# OLM-base_v_REVG.net
KiCad netlist of a schematic drawn in EAGLE
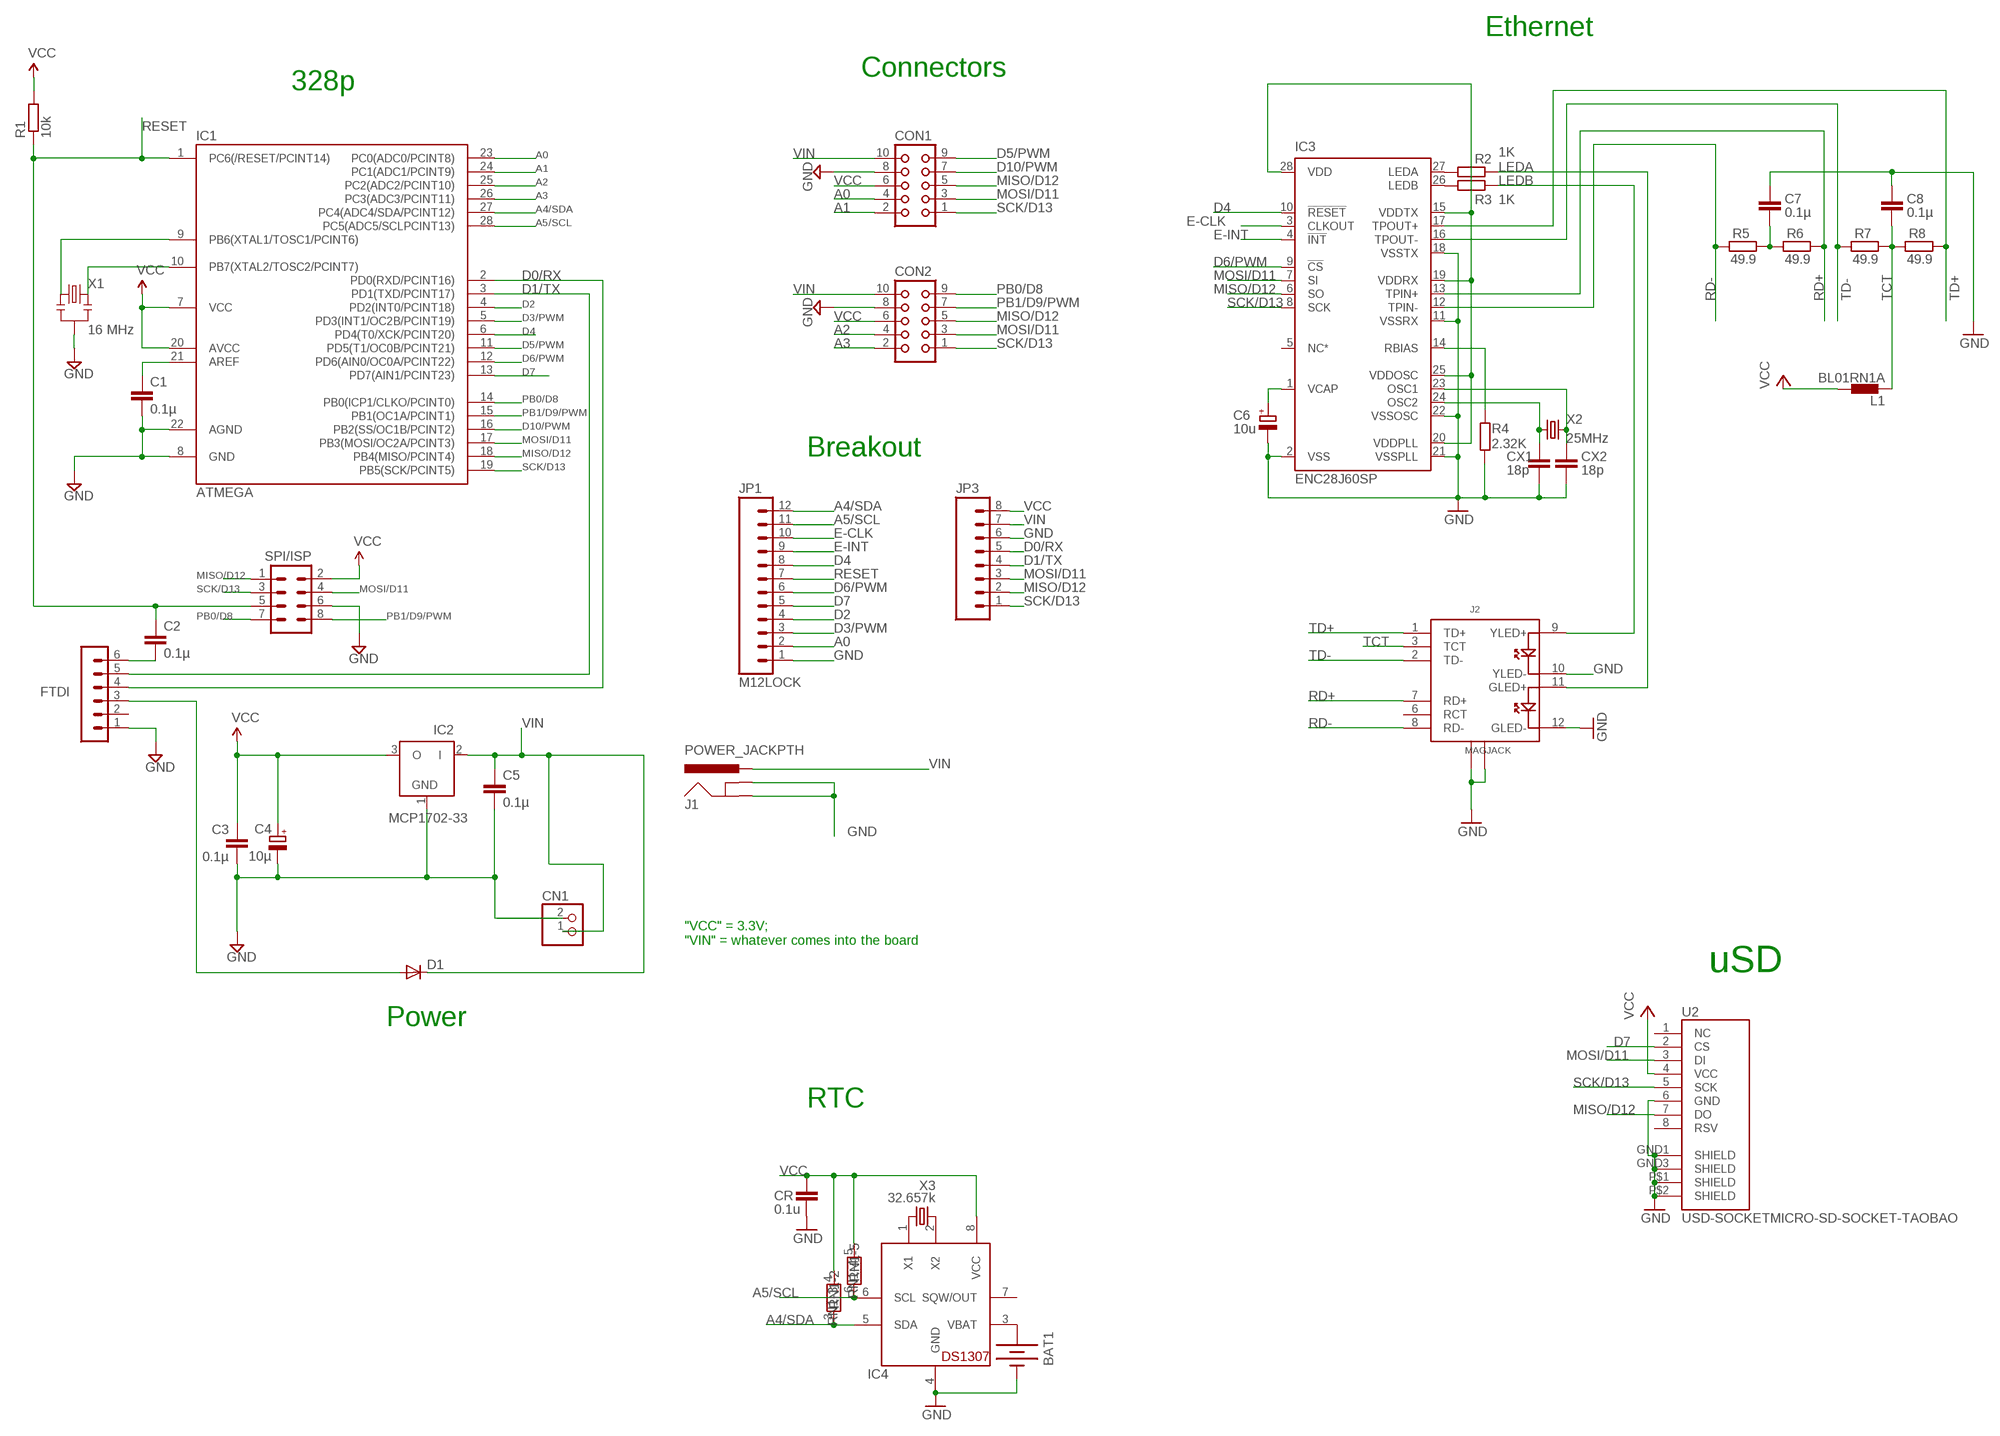
[diagram p0: schematic, sheet 1]

(export (version "E")
  (design (tool "Eeschema 10.0.6"))
  (components
    (comp (ref "BAT1")
      (value "BATTERY12PTH")
      (footprint "eagle-import:BATTCON_12MM_PTH")
      (libsource (lib "eagle-import") (part "BATTERY12PTH"))
    )
    (comp (ref "C1")
      (value "0.1µ")
      (footprint "eagle-import:C025-024X044")
      (libsource (lib "eagle-import") (part "resistor_C-EU025-024X044"))
    )
    (comp (ref "C2")
      (value "0.1µ")
      (footprint "eagle-import:C025-024X044")
      (libsource (lib "eagle-import") (part "resistor_C-EU025-024X044"))
    )
    (comp (ref "C3")
      (value "0.1µ")
      (footprint "eagle-import:C025-024X044")
      (libsource (lib "eagle-import") (part "resistor_C-EU025-024X044"))
    )
    (comp (ref "C4")
      (value "10µ")
      (footprint "eagle-import:E1,8-4")
      (libsource (lib "eagle-import") (part "CPOL-EUE1.8-4"))
    )
    (comp (ref "C5")
      (value "0.1µ")
      (footprint "eagle-import:C025-024X044")
      (libsource (lib "eagle-import") (part "resistor_C-EU025-024X044"))
    )
    (comp (ref "C6")
      (value "10u")
      (footprint "eagle-import:E1,8-4")
      (libsource (lib "eagle-import") (part "CPOL-EUE1.8-4"))
    )
    (comp (ref "C7")
      (value "0.1µ")
      (footprint "eagle-import:C025-024X044")
      (libsource (lib "eagle-import") (part "resistor_C-EU025-024X044"))
    )
    (comp (ref "C8")
      (value "0.1µ")
      (footprint "eagle-import:C025-024X044")
      (libsource (lib "eagle-import") (part "resistor_C-EU025-024X044"))
    )
    (comp (ref "CN1")
      (value "JST_2PIN-THM-RA")
      (footprint "eagle-import:JST-PH-2-THM-RA")
      (libsource (lib "eagle-import") (part "JST_2PIN-THM-RA"))
    )
    (comp (ref "CON1")
      (value "CON10L")
      (footprint "eagle-import:CON10L")
      (libsource (lib "eagle-import") (part "CON10L"))
    )
    (comp (ref "CON2")
      (value "CON10L")
      (footprint "eagle-import:CON10L")
      (libsource (lib "eagle-import") (part "CON10L"))
    )
    (comp (ref "CR")
      (value "0.1u")
      (footprint "eagle-import:C025-024X044")
      (libsource (lib "eagle-import") (part "C-EU025-024X044"))
    )
    (comp (ref "CX1")
      (value "18p")
      (footprint "eagle-import:C025-024X044")
      (libsource (lib "eagle-import") (part "resistor_C-EU025-024X044"))
    )
    (comp (ref "CX2")
      (value "18p")
      (footprint "eagle-import:C025-024X044")
      (libsource (lib "eagle-import") (part "resistor_C-EU025-024X044"))
    )
    (comp (ref "D1")
      (value "DIODE-D-5")
      (footprint "eagle-import:D-5")
      (libsource (lib "eagle-import") (part "DIODE-D-5"))
    )
    (comp (ref "FTDI")
      (value "FTDI")
      (footprint "eagle-import:MA06-1")
      (libsource (lib "eagle-import") (part "MA06-1"))
    )
    (comp (ref "IC1")
      (value "ATMEGA")
      (footprint "eagle-import:DIL28-3")
      (libsource (lib "eagle-import") (part "ATMEGA48/88/168-PU"))
    )
    (comp (ref "IC2")
      (value "MCP1702-33")
      (footprint "eagle-import:TO92")
      (libsource (lib "eagle-import") (part "MCP1702Z"))
    )
    (comp (ref "IC3")
      (value "ENC28J60SP")
      (footprint "eagle-import:DIL28-3")
      (fields (field (name "MF") "MICROCHIP") (field (name "MPN") "ENC28J60/SP"))
      (libsource (lib "eagle-import") (part "ENC28J60SP"))
    )
    (comp (ref "IC4")
      (value "DS1307")
      (footprint "eagle-import:DIL08")
      (libsource (lib "eagle-import") (part "DS1307"))
    )
    (comp (ref "J1")
      (value "POWER_JACKPTH")
      (footprint "eagle-import:POWER_JACK_PTH")
      (libsource (lib "eagle-import") (part "POWER_JACKPTH"))
    )
    (comp (ref "J2")
      (value "MAGJACK")
      (footprint "eagle-import:MAGJACK")
      (libsource (lib "eagle-import") (part "MAGJACK"))
    )
    (comp (ref "JP1")
      (value "M12LOCK")
      (footprint "eagle-import:1X12_LOCK")
      (libsource (lib "eagle-import") (part "M12LOCK"))
    )
    (comp (ref "JP3")
      (value "M08LOCK")
      (footprint "eagle-import:1X08_LOCK")
      (libsource (lib "eagle-import") (part "M08LOCK"))
    )
    (comp (ref "L1")
      (value "BL01RN1A")
      (footprint "eagle-import:BL01RN1A")
      (libsource (lib "eagle-import") (part "BL01RN1A"))
    )
    (comp (ref "R1")
      (value "10k")
      (footprint "eagle-import:0204_7")
      (libsource (lib "eagle-import") (part "resistor_R-EU_0204/7"))
    )
    (comp (ref "R2")
      (value "1K")
      (footprint "eagle-import:0204_7")
      (libsource (lib "eagle-import") (part "R-EU_0204/7"))
    )
    (comp (ref "R3")
      (value "1K")
      (footprint "eagle-import:0204_7")
      (libsource (lib "eagle-import") (part "R-EU_0204/7"))
    )
    (comp (ref "R4")
      (value "2.32K")
      (footprint "eagle-import:0204_7")
      (libsource (lib "eagle-import") (part "R-EU_0204/7"))
    )
    (comp (ref "R5")
      (value "49.9")
      (footprint "eagle-import:0204_7")
      (libsource (lib "eagle-import") (part "R-EU_0204/7"))
    )
    (comp (ref "R6")
      (value "49.9")
      (footprint "eagle-import:0204_7")
      (libsource (lib "eagle-import") (part "R-EU_0204/7"))
    )
    (comp (ref "R7")
      (value "49.9")
      (footprint "eagle-import:0204_7")
      (libsource (lib "eagle-import") (part "R-EU_0204/7"))
    )
    (comp (ref "R8")
      (value "49.9")
      (footprint "eagle-import:0204_7")
      (libsource (lib "eagle-import") (part "R-EU_0204/7"))
    )
    (comp (ref "RN1")
      (value "RNX7")
      (footprint "eagle-import:RN-8")
      (libsource (lib "eagle-import") (part "RNX7"))
    )
    (comp (ref "SV1")
      (value "SPI/ISP")
      (footprint "eagle-import:MA04-2")
      (libsource (lib "eagle-import") (part "MA04-2"))
    )
    (comp (ref "U2")
      (value "USD-SOCKETMICRO-SD-SOCKET-TAOBAO")
      (footprint "eagle-import:MICRO-SD-SOCKET-TAOBAO")
      (libsource (lib "eagle-import") (part "USD-SOCKETMICRO-SD-SOCKET-TAOBAO"))
    )
    (comp (ref "X1")
      (value "16 MHz")
      (footprint "eagle-import:RESONATOR-PTH")
      (libsource (lib "eagle-import") (part "RESONATORPTH"))
    )
    (comp (ref "X2")
      (value "25MHz")
      (footprint "eagle-import:HC49US")
      (libsource (lib "eagle-import") (part "CRYSTALHC49US"))
    )
    (comp (ref "X3")
      (value "32.657k")
      (footprint "eagle-import:TC26H")
      (libsource (lib "eagle-import") (part "crystal_CRYSTALTC26H"))
    )
  )
  (nets
    (net (code "1") (name "/A0") (class "Default")
      (node (ref "CON1") (pin "4") (pinfunction "4_4") (pintype "passive"))
      (node (ref "IC1") (pin "23") (pinfunction "PC0(ADC0/PCINT8)_23") (pintype "bidirectional"))
      (node (ref "JP1") (pin "2") (pinfunction "2_2") (pintype "passive"))
    )
    (net (code "2") (name "/A1") (class "Default")
      (node (ref "CON1") (pin "2") (pinfunction "2_2") (pintype "passive"))
      (node (ref "IC1") (pin "24") (pinfunction "PC1(ADC1/PCINT9)_24") (pintype "bidirectional"))
    )
    (net (code "3") (name "/A2") (class "Default")
      (node (ref "CON2") (pin "4") (pinfunction "4_4") (pintype "passive"))
      (node (ref "IC1") (pin "25") (pinfunction "PC2(ADC2/PCINT10)_25") (pintype "bidirectional"))
    )
    (net (code "4") (name "/A3") (class "Default")
      (node (ref "CON2") (pin "2") (pinfunction "2_2") (pintype "passive"))
      (node (ref "IC1") (pin "26") (pinfunction "PC3(ADC3/PCINT11)_26") (pintype "bidirectional"))
    )
    (net (code "5") (name "/A4{slash}SDA") (class "Default")
      (node (ref "IC1") (pin "27") (pinfunction "PC4(ADC4/SDA/PCINT12)_27") (pintype "bidirectional"))
      (node (ref "IC4") (pin "5") (pinfunction "SDA_5") (pintype "bidirectional"))
      (node (ref "JP1") (pin "12") (pinfunction "12_12") (pintype "passive"))
      (node (ref "RN1") (pin "3") (pinfunction "1_3") (pintype "passive"))
    )
    (net (code "6") (name "/A5{slash}SCL") (class "Default")
      (node (ref "IC1") (pin "28") (pinfunction "PC5(ADC5/SCLPCINT13)_28") (pintype "bidirectional"))
      (node (ref "IC4") (pin "6") (pinfunction "SCL_6") (pintype "bidirectional"))
      (node (ref "JP1") (pin "11") (pinfunction "11_11") (pintype "passive"))
      (node (ref "RN1") (pin "6") (pinfunction "1_6") (pintype "passive"))
    )
    (net (code "7") (name "/D0{slash}RX") (class "Default")
      (node (ref "FTDI") (pin "4") (pinfunction "4_4") (pintype "passive"))
      (node (ref "IC1") (pin "2") (pinfunction "PD0(RXD/PCINT16)_2") (pintype "bidirectional"))
      (node (ref "JP3") (pin "5") (pinfunction "5_5") (pintype "passive"))
    )
    (net (code "8") (name "/D1{slash}TX") (class "Default")
      (node (ref "FTDI") (pin "5") (pinfunction "5_5") (pintype "passive"))
      (node (ref "IC1") (pin "3") (pinfunction "PD1(TXD/PCINT17)_3") (pintype "bidirectional"))
      (node (ref "JP3") (pin "4") (pinfunction "4_4") (pintype "passive"))
    )
    (net (code "9") (name "/D2") (class "Default")
      (node (ref "IC1") (pin "4") (pinfunction "PD2(INT0/PCINT18)_4") (pintype "bidirectional"))
      (node (ref "JP1") (pin "4") (pinfunction "4_4") (pintype "passive"))
    )
    (net (code "10") (name "/D3{slash}PWM") (class "Default")
      (node (ref "IC1") (pin "5") (pinfunction "PD3(INT1/OC2B/PCINT19)_5") (pintype "bidirectional"))
      (node (ref "JP1") (pin "3") (pinfunction "3_3") (pintype "passive"))
    )
    (net (code "11") (name "/D4") (class "Default")
      (node (ref "IC1") (pin "6") (pinfunction "PD4(T0/XCK/PCINT20)_6") (pintype "bidirectional"))
      (node (ref "IC3") (pin "10") (pinfunction "~{RESET}_10") (pintype "input"))
      (node (ref "JP1") (pin "8") (pinfunction "8_8") (pintype "passive"))
    )
    (net (code "12") (name "/D5{slash}PWM") (class "Default")
      (node (ref "CON1") (pin "9") (pinfunction "9_9") (pintype "passive"))
      (node (ref "IC1") (pin "11") (pinfunction "PD5(T1/OC0B/PCINT21)_11") (pintype "bidirectional"))
    )
    (net (code "13") (name "/D6{slash}PWM") (class "Default")
      (node (ref "IC1") (pin "12") (pinfunction "PD6(AIN0/OC0A/PCINT22)_12") (pintype "bidirectional"))
      (node (ref "IC3") (pin "9") (pinfunction "~{CS}_9") (pintype "input"))
      (node (ref "JP1") (pin "6") (pinfunction "6_6") (pintype "passive"))
    )
    (net (code "14") (name "/D7") (class "Default")
      (node (ref "IC1") (pin "13") (pinfunction "PD7(AIN1/PCINT23)_13") (pintype "bidirectional"))
      (node (ref "JP1") (pin "5") (pinfunction "5_5") (pintype "passive"))
      (node (ref "U2") (pin "2") (pinfunction "CS_2") (pintype "bidirectional"))
    )
    (net (code "15") (name "/D10{slash}PWM") (class "Default")
      (node (ref "CON1") (pin "7") (pinfunction "7_7") (pintype "passive"))
      (node (ref "IC1") (pin "16") (pinfunction "PB2(SS/OC1B/PCINT2)_16") (pintype "bidirectional"))
    )
    (net (code "16") (name "/E-CLK") (class "Default")
      (node (ref "IC3") (pin "3") (pinfunction "CLKOUT_3") (pintype "output"))
      (node (ref "JP1") (pin "10") (pinfunction "10_10") (pintype "passive"))
    )
    (net (code "17") (name "/E-INT") (class "Default")
      (node (ref "IC3") (pin "4") (pinfunction "~{INT}_4") (pintype "output"))
      (node (ref "JP1") (pin "9") (pinfunction "9_9") (pintype "passive"))
    )
    (net (code "18") (name "/LEDA") (class "Default")
      (node (ref "J2") (pin "11") (pinfunction "GLED+_11") (pintype "bidirectional"))
      (node (ref "R2") (pin "2") (pinfunction "2_2") (pintype "passive"))
    )
    (net (code "19") (name "/LEDB") (class "Default")
      (node (ref "J2") (pin "9") (pinfunction "YLED+_9") (pintype "bidirectional"))
      (node (ref "R3") (pin "2") (pinfunction "2_2") (pintype "passive"))
    )
    (net (code "20") (name "/MISO{slash}D12") (class "Default")
      (node (ref "CON1") (pin "5") (pinfunction "5_5") (pintype "passive"))
      (node (ref "CON2") (pin "5") (pinfunction "5_5") (pintype "passive"))
      (node (ref "IC1") (pin "18") (pinfunction "PB4(MISO/PCINT4)_18") (pintype "bidirectional"))
      (node (ref "IC3") (pin "6") (pinfunction "SO_6") (pintype "output"))
      (node (ref "JP3") (pin "2") (pinfunction "2_2") (pintype "passive"))
      (node (ref "SV1") (pin "1") (pinfunction "1_1") (pintype "passive"))
      (node (ref "U2") (pin "7") (pinfunction "DO_7") (pintype "bidirectional"))
    )
    (net (code "21") (name "/MOSI{slash}D11") (class "Default")
      (node (ref "CON1") (pin "3") (pinfunction "3_3") (pintype "passive"))
      (node (ref "CON2") (pin "3") (pinfunction "3_3") (pintype "passive"))
      (node (ref "IC1") (pin "17") (pinfunction "PB3(MOSI/OC2A/PCINT3)_17") (pintype "bidirectional"))
      (node (ref "IC3") (pin "7") (pinfunction "SI_7") (pintype "input"))
      (node (ref "JP3") (pin "3") (pinfunction "3_3") (pintype "passive"))
      (node (ref "SV1") (pin "4") (pinfunction "4_4") (pintype "passive"))
      (node (ref "U2") (pin "3") (pinfunction "DI_3") (pintype "bidirectional"))
    )
    (net (code "22") (name "/PB0{slash}D8") (class "Default")
      (node (ref "CON2") (pin "9") (pinfunction "9_9") (pintype "passive"))
      (node (ref "IC1") (pin "14") (pinfunction "PB0(ICP1/CLKO/PCINT0)_14") (pintype "bidirectional"))
      (node (ref "SV1") (pin "7") (pinfunction "7_7") (pintype "passive"))
    )
    (net (code "23") (name "/PB1{slash}D9{slash}PWM") (class "Default")
      (node (ref "CON2") (pin "7") (pinfunction "7_7") (pintype "passive"))
      (node (ref "IC1") (pin "15") (pinfunction "PB1(OC1A/PCINT1)_15") (pintype "bidirectional"))
      (node (ref "SV1") (pin "8") (pinfunction "8_8") (pintype "passive"))
    )
    (net (code "24") (name "/RD+") (class "Default")
      (node (ref "IC3") (pin "13") (pinfunction "TPIN+_13") (pintype "input"))
      (node (ref "J2") (pin "7") (pinfunction "RD+_7") (pintype "bidirectional"))
      (node (ref "R6") (pin "2") (pinfunction "2_2") (pintype "passive"))
    )
    (net (code "25") (name "/RD-") (class "Default")
      (node (ref "IC3") (pin "12") (pinfunction "TPIN-_12") (pintype "input"))
      (node (ref "J2") (pin "8") (pinfunction "RD-_8") (pintype "bidirectional"))
      (node (ref "R5") (pin "1") (pinfunction "1_1") (pintype "passive"))
    )
    (net (code "26") (name "/RESET") (class "Default")
      (node (ref "C2") (pin "1") (pinfunction "1_1") (pintype "passive"))
      (node (ref "IC1") (pin "1") (pinfunction "PC6(/RESET/PCINT14)_1") (pintype "bidirectional"))
      (node (ref "JP1") (pin "7") (pinfunction "7_7") (pintype "passive"))
      (node (ref "R1") (pin "1") (pinfunction "1_1") (pintype "passive"))
      (node (ref "SV1") (pin "5") (pinfunction "5_5") (pintype "passive"))
    )
    (net (code "27") (name "/SCK{slash}D13") (class "Default")
      (node (ref "CON1") (pin "1") (pinfunction "1_1") (pintype "passive"))
      (node (ref "CON2") (pin "1") (pinfunction "1_1") (pintype "passive"))
      (node (ref "IC1") (pin "19") (pinfunction "PB5(SCK/PCINT5)_19") (pintype "bidirectional"))
      (node (ref "IC3") (pin "8") (pinfunction "SCK_8") (pintype "input"))
      (node (ref "JP3") (pin "1") (pinfunction "1_1") (pintype "passive"))
      (node (ref "SV1") (pin "3") (pinfunction "3_3") (pintype "passive"))
      (node (ref "U2") (pin "5") (pinfunction "SCK_5") (pintype "bidirectional"))
    )
    (net (code "28") (name "/TCT") (class "Default")
      (node (ref "C8") (pin "2") (pinfunction "2_2") (pintype "passive"))
      (node (ref "J2") (pin "3") (pinfunction "TCT_3") (pintype "bidirectional"))
      (node (ref "L1") (pin "1") (pinfunction "1_1") (pintype "passive"))
      (node (ref "R7") (pin "2") (pinfunction "2_2") (pintype "passive"))
      (node (ref "R8") (pin "1") (pinfunction "1_1") (pintype "passive"))
    )
    (net (code "29") (name "/TD+") (class "Default")
      (node (ref "IC3") (pin "17") (pinfunction "TPOUT+_17") (pintype "output"))
      (node (ref "J2") (pin "1") (pinfunction "TD+_1") (pintype "bidirectional"))
      (node (ref "R8") (pin "2") (pinfunction "2_2") (pintype "passive"))
    )
    (net (code "30") (name "/TD-") (class "Default")
      (node (ref "IC3") (pin "16") (pinfunction "TPOUT-_16") (pintype "output"))
      (node (ref "J2") (pin "2") (pinfunction "TD-_2") (pintype "bidirectional"))
      (node (ref "R7") (pin "1") (pinfunction "1_1") (pintype "passive"))
    )
    (net (code "31") (name "/VIN") (class "Default")
      (node (ref "C5") (pin "1") (pinfunction "1_1") (pintype "passive"))
      (node (ref "CN1") (pin "1") (pinfunction "2_1") (pintype "passive"))
      (node (ref "CON1") (pin "10") (pinfunction "10_10") (pintype "passive"))
      (node (ref "CON2") (pin "10") (pinfunction "10_10") (pintype "passive"))
      (node (ref "D1") (pin "C") (pinfunction "C_C") (pintype "passive"))
      (node (ref "IC2") (pin "2") (pinfunction "I_2") (pintype "input"))
      (node (ref "J1") (pin "PWR") (pinfunction "PWR_PWR") (pintype "bidirectional"))
      (node (ref "JP3") (pin "7") (pinfunction "7_7") (pintype "passive"))
    )
    (net (code "32") (name "GND") (class "Default")
      (node (ref "BAT1") (pin "GND") (pinfunction "-_GND") (pintype "power_in"))
      (node (ref "C1") (pin "2") (pinfunction "2_2") (pintype "passive"))
      (node (ref "C3") (pin "2") (pinfunction "2_2") (pintype "passive"))
      (node (ref "C4") (pin "-") (pinfunction "-_-") (pintype "passive"))
      (node (ref "C5") (pin "2") (pinfunction "2_2") (pintype "passive"))
      (node (ref "C6") (pin "-") (pinfunction "-_-") (pintype "passive"))
      (node (ref "C7") (pin "1") (pinfunction "1_1") (pintype "passive"))
      (node (ref "C8") (pin "1") (pinfunction "1_1") (pintype "passive"))
      (node (ref "CN1") (pin "2") (pinfunction "1_2") (pintype "passive"))
      (node (ref "CON1") (pin "8") (pinfunction "8_8") (pintype "passive"))
      (node (ref "CON2") (pin "8") (pinfunction "8_8") (pintype "passive"))
      (node (ref "CR") (pin "2") (pinfunction "2_2") (pintype "passive"))
      (node (ref "CX1") (pin "2") (pinfunction "2_2") (pintype "passive"))
      (node (ref "CX2") (pin "2") (pinfunction "2_2") (pintype "passive"))
      (node (ref "FTDI") (pin "1") (pinfunction "1_1") (pintype "passive"))
      (node (ref "IC1") (pin "22") (pinfunction "AGND_22") (pintype "power_in"))
      (node (ref "IC1") (pin "8") (pinfunction "GND_8") (pintype "power_in"))
      (node (ref "IC2") (pin "1") (pinfunction "GND_1") (pintype "power_in"))
      (node (ref "IC3") (pin "11") (pinfunction "VSSRX_11") (pintype "input"))
      (node (ref "IC3") (pin "18") (pinfunction "VSSTX_18") (pintype "input"))
      (node (ref "IC3") (pin "2") (pinfunction "VSS_2") (pintype "input"))
      (node (ref "IC3") (pin "21") (pinfunction "VSSPLL_21") (pintype "input"))
      (node (ref "IC3") (pin "22") (pinfunction "VSSOSC_22") (pintype "input"))
      (node (ref "IC4") (pin "4") (pinfunction "GND_4") (pintype "power_in"))
      (node (ref "J1") (pin "GND") (pinfunction "GND_GND") (pintype "bidirectional"))
      (node (ref "J1") (pin "GNDBREAK") (pinfunction "GNDBREAK_GNDBREAK") (pintype "bidirectional"))
      (node (ref "J2") (pin "10") (pinfunction "YLED-_10") (pintype "bidirectional"))
      (node (ref "J2") (pin "12") (pinfunction "GLED-_12") (pintype "bidirectional"))
      (node (ref "J2") (pin "M1") (pinfunction "GND1_M1") (pintype "bidirectional"))
      (node (ref "J2") (pin "M2") (pinfunction "GND2_M2") (pintype "bidirectional"))
      (node (ref "JP1") (pin "1") (pinfunction "1_1") (pintype "passive"))
      (node (ref "JP3") (pin "6") (pinfunction "6_6") (pintype "passive"))
      (node (ref "R4") (pin "2") (pinfunction "2_2") (pintype "passive"))
      (node (ref "SV1") (pin "6") (pinfunction "6_6") (pintype "passive"))
      (node (ref "U2") (pin "6") (pinfunction "GND_6") (pintype "bidirectional"))
      (node (ref "U2") (pin "GND1") (pinfunction "SHIELD_GND1") (pintype "bidirectional"))
      (node (ref "U2") (pin "GND3") (pinfunction "SHIELD_GND3") (pintype "bidirectional"))
      (node (ref "U2") (pin "P$1") (pinfunction "SHIELD_P$1") (pintype "bidirectional"))
      (node (ref "U2") (pin "P$2") (pinfunction "SHIELD_P$2") (pintype "bidirectional"))
      (node (ref "X1") (pin "2") (pinfunction "2_2") (pintype "passive"))
    )
    (net (code "33") (name "Net-(BAT1-+)") (class "Default")
      (node (ref "BAT1") (pin "VCC@1") (pinfunction "+_VCC@1") (pintype "power_in"))
      (node (ref "IC4") (pin "3") (pinfunction "VBAT_3") (pintype "power_in"))
    )
    (net (code "34") (name "Net-(C2-Pad2)") (class "Default")
      (node (ref "C2") (pin "2") (pinfunction "2_2") (pintype "passive"))
      (node (ref "FTDI") (pin "6") (pinfunction "6_6") (pintype "passive"))
    )
    (net (code "35") (name "Net-(C7-Pad2)") (class "Default")
      (node (ref "C7") (pin "2") (pinfunction "2_2") (pintype "passive"))
      (node (ref "R5") (pin "2") (pinfunction "2_2") (pintype "passive"))
      (node (ref "R6") (pin "1") (pinfunction "1_1") (pintype "passive"))
    )
    (net (code "36") (name "Net-(D1-PadA)") (class "Default")
      (node (ref "D1") (pin "A") (pinfunction "A_A") (pintype "passive"))
      (node (ref "FTDI") (pin "3") (pinfunction "3_3") (pintype "passive"))
    )
    (net (code "37") (name "Net-(IC1-AREF)") (class "Default")
      (node (ref "C1") (pin "1") (pinfunction "1_1") (pintype "passive"))
      (node (ref "IC1") (pin "21") (pinfunction "AREF_21") (pintype "passive"))
    )
    (net (code "38") (name "Net-(IC1-PB6(XTAL1{slash}TOSC1{slash}PCINT6))") (class "Default")
      (node (ref "IC1") (pin "9") (pinfunction "PB6(XTAL1/TOSC1/PCINT6)_9") (pintype "bidirectional"))
      (node (ref "X1") (pin "1") (pinfunction "1_1") (pintype "passive"))
    )
    (net (code "39") (name "Net-(IC1-PB7(XTAL2{slash}TOSC2{slash}PCINT7))") (class "Default")
      (node (ref "IC1") (pin "10") (pinfunction "PB7(XTAL2/TOSC2/PCINT7)_10") (pintype "bidirectional"))
      (node (ref "X1") (pin "3") (pinfunction "3_3") (pintype "passive"))
    )
    (net (code "40") (name "Net-(IC3-LEDA)") (class "Default")
      (node (ref "IC3") (pin "27") (pinfunction "LEDA_27") (pintype "output"))
      (node (ref "R2") (pin "1") (pinfunction "1_1") (pintype "passive"))
    )
    (net (code "41") (name "Net-(IC3-LEDB)") (class "Default")
      (node (ref "IC3") (pin "26") (pinfunction "LEDB_26") (pintype "output"))
      (node (ref "R3") (pin "1") (pinfunction "1_1") (pintype "passive"))
    )
    (net (code "42") (name "Net-(IC3-OSC1)") (class "Default")
      (node (ref "CX2") (pin "1") (pinfunction "1_1") (pintype "passive"))
      (node (ref "IC3") (pin "23") (pinfunction "OSC1_23") (pintype "input"))
      (node (ref "X2") (pin "2") (pinfunction "2_2") (pintype "passive"))
    )
    (net (code "43") (name "Net-(IC3-OSC2)") (class "Default")
      (node (ref "CX1") (pin "1") (pinfunction "1_1") (pintype "passive"))
      (node (ref "IC3") (pin "24") (pinfunction "OSC2_24") (pintype "output"))
      (node (ref "X2") (pin "1") (pinfunction "1_1") (pintype "passive"))
    )
    (net (code "44") (name "Net-(IC3-RBIAS)") (class "Default")
      (node (ref "IC3") (pin "14") (pinfunction "RBIAS_14") (pintype "input"))
      (node (ref "R4") (pin "1") (pinfunction "1_1") (pintype "passive"))
    )
    (net (code "45") (name "Net-(IC3-VCAP)") (class "Default")
      (node (ref "C6") (pin "+") (pinfunction "+_+") (pintype "passive"))
      (node (ref "IC3") (pin "1") (pinfunction "VCAP_1") (pintype "input"))
    )
    (net (code "46") (name "Net-(IC4-X1)") (class "Default")
      (node (ref "IC4") (pin "1") (pinfunction "X1_1") (pintype "passive"))
      (node (ref "X3") (pin "1") (pinfunction "1_1") (pintype "passive"))
    )
    (net (code "47") (name "Net-(IC4-X2)") (class "Default")
      (node (ref "IC4") (pin "2") (pinfunction "X2_2") (pintype "passive"))
      (node (ref "X3") (pin "2") (pinfunction "2_2") (pintype "passive"))
    )
    (net (code "48") (name "VCC") (class "Default")
      (node (ref "C3") (pin "1") (pinfunction "1_1") (pintype "passive"))
      (node (ref "C4") (pin "+") (pinfunction "+_+") (pintype "passive"))
      (node (ref "CON1") (pin "6") (pinfunction "6_6") (pintype "passive"))
      (node (ref "CON2") (pin "6") (pinfunction "6_6") (pintype "passive"))
      (node (ref "CR") (pin "1") (pinfunction "1_1") (pintype "passive"))
      (node (ref "IC1") (pin "20") (pinfunction "AVCC_20") (pintype "passive"))
      (node (ref "IC1") (pin "7") (pinfunction "VCC_7") (pintype "power_in"))
      (node (ref "IC2") (pin "3") (pinfunction "O_3") (pintype "input"))
      (node (ref "IC3") (pin "15") (pinfunction "VDDTX_15") (pintype "input"))
      (node (ref "IC3") (pin "19") (pinfunction "VDDRX_19") (pintype "input"))
      (node (ref "IC3") (pin "20") (pinfunction "VDDPLL_20") (pintype "input"))
      (node (ref "IC3") (pin "25") (pinfunction "VDDOSC_25") (pintype "input"))
      (node (ref "IC3") (pin "28") (pinfunction "VDD_28") (pintype "input"))
      (node (ref "IC4") (pin "8") (pinfunction "VCC_8") (pintype "power_in"))
      (node (ref "JP3") (pin "8") (pinfunction "8_8") (pintype "passive"))
      (node (ref "L1") (pin "2") (pinfunction "2_2") (pintype "passive"))
      (node (ref "R1") (pin "2") (pinfunction "2_2") (pintype "passive"))
      (node (ref "RN1") (pin "4") (pinfunction "1_4") (pintype "passive"))
      (node (ref "RN1") (pin "5") (pinfunction "1_5") (pintype "passive"))
      (node (ref "SV1") (pin "2") (pinfunction "2_2") (pintype "passive"))
      (node (ref "U2") (pin "4") (pinfunction "VCC_4") (pintype "bidirectional"))
    )
    (net (code "49") (name "unconnected-(FTDI-Pad2)") (class "Default")
      (node (ref "FTDI") (pin "2") (pinfunction "2_2") (pintype "passive"))
    )
    (net (code "50") (name "unconnected-(IC3-NC*-Pad5)") (class "Default")
      (node (ref "IC3") (pin "5") (pinfunction "NC*_5") (pintype "output"))
    )
    (net (code "51") (name "unconnected-(IC4-SQW{slash}OUT-Pad7)") (class "Default")
      (node (ref "IC4") (pin "7") (pinfunction "SQW/OUT_7") (pintype "bidirectional"))
    )
    (net (code "52") (name "unconnected-(J2-RCT-Pad6)") (class "Default")
      (node (ref "J2") (pin "6") (pinfunction "RCT_6") (pintype "bidirectional"))
    )
    (net (code "53") (name "unconnected-(U2-NC-Pad1)") (class "Default")
      (node (ref "U2") (pin "1") (pinfunction "NC_1") (pintype "bidirectional"))
    )
    (net (code "54") (name "unconnected-(U2-RSV-Pad8)") (class "Default")
      (node (ref "U2") (pin "8") (pinfunction "RSV_8") (pintype "bidirectional"))
    )
  )
)
